# Qwiic_Pi_SHIM.net
KiCad netlist of a schematic drawn in EAGLE
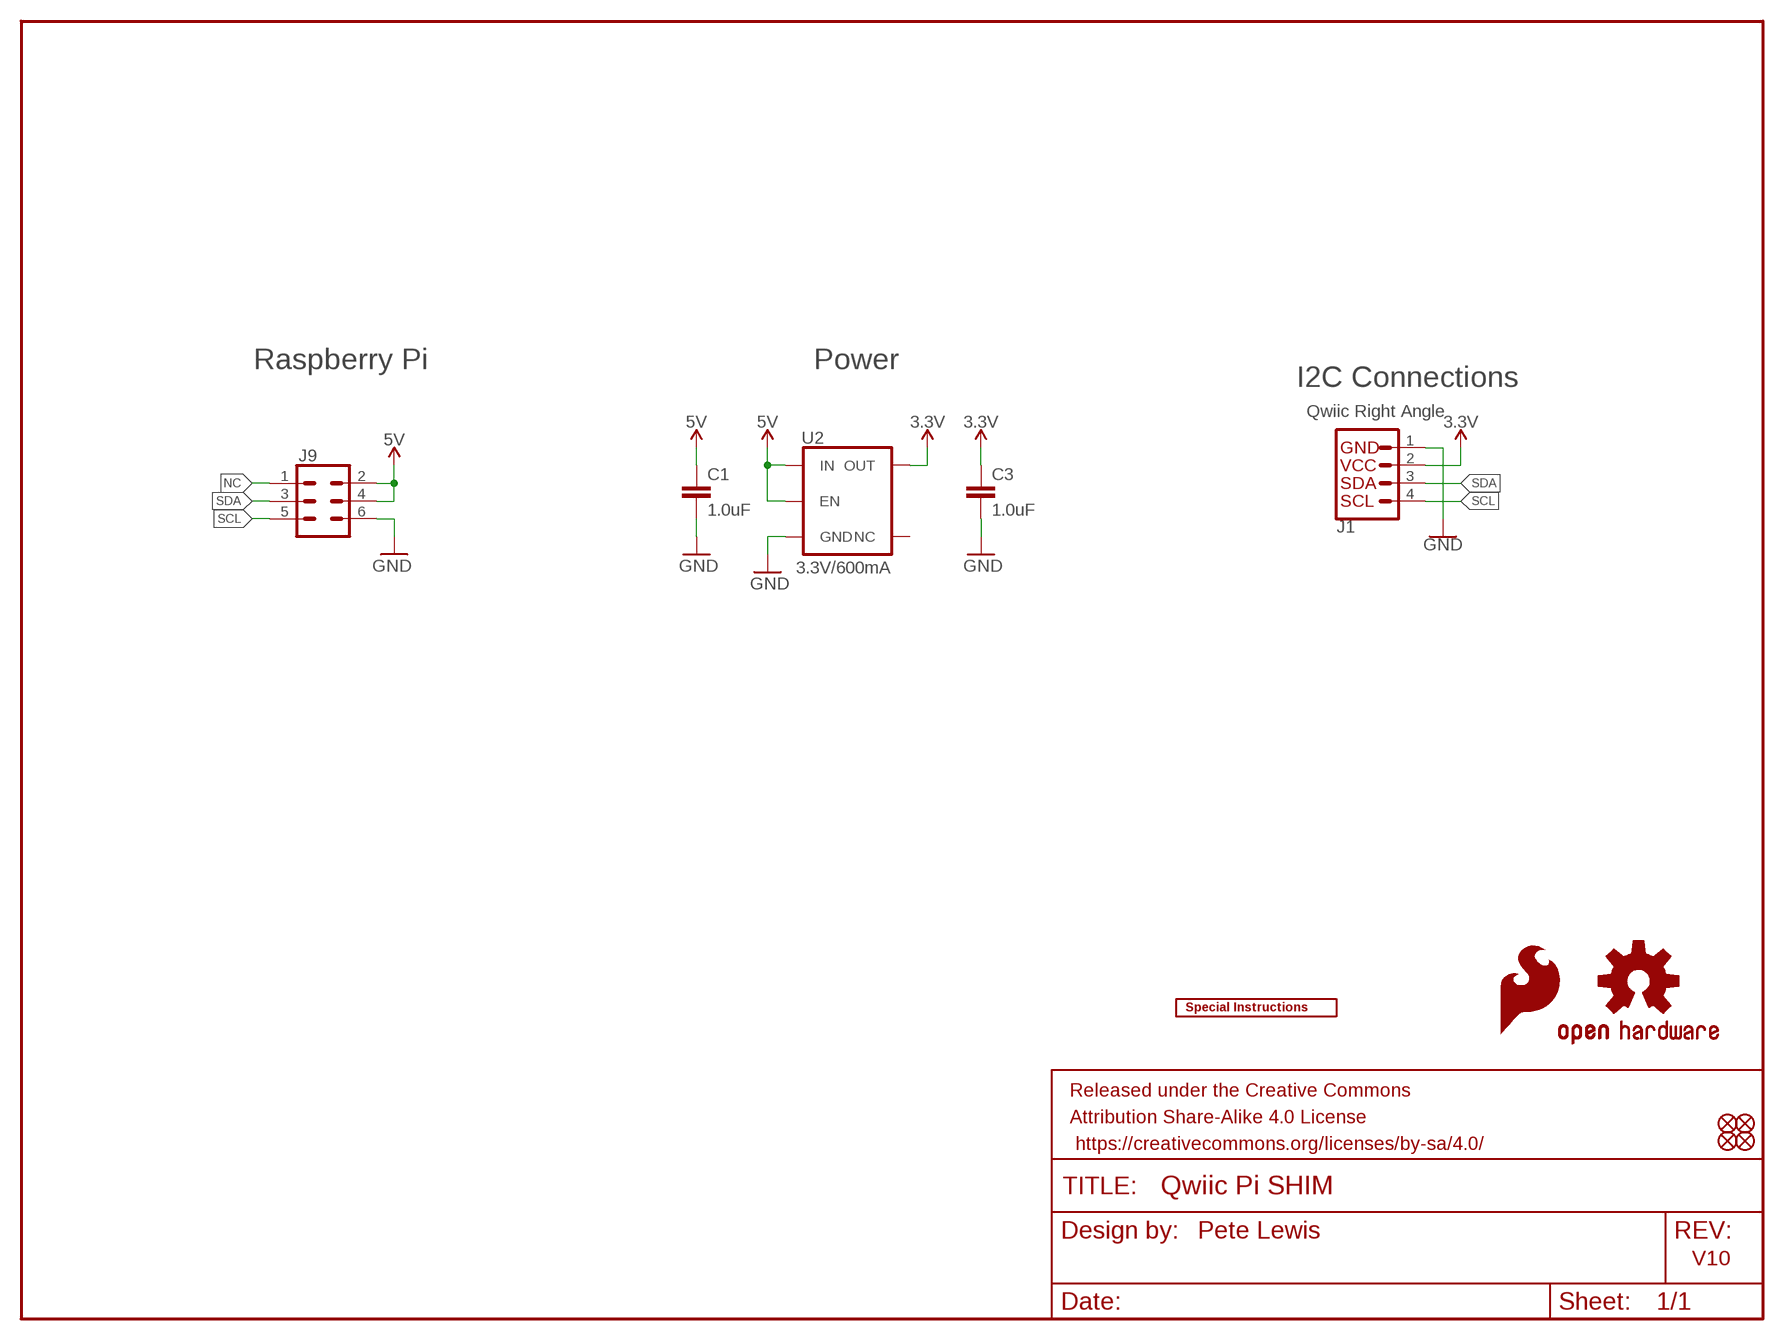
[diagram p0: schematic, sheet 1]

(export (version "E")
  (design (tool "Eeschema 10.0.6"))
  (components
    (comp (ref "C1")
      (value "1.0uF")
      (footprint "eagle-import:0603")
      (libsource (lib "eagle-import") (part "1.0UF-0603-16V-10%"))
    )
    (comp (ref "C3")
      (value "1.0uF")
      (footprint "eagle-import:0603")
      (libsource (lib "eagle-import") (part "1.0UF-0603-16V-10%"))
    )
    (comp (ref "FD1")
      (value "FIDUCIALUFIDUCIAL")
      (footprint "eagle-import:FIDUCIAL-MICRO")
      (libsource (lib "eagle-import") (part "FIDUCIALUFIDUCIAL"))
    )
    (comp (ref "FD2")
      (value "FIDUCIALUFIDUCIAL")
      (footprint "eagle-import:FIDUCIAL-MICRO")
      (libsource (lib "eagle-import") (part "FIDUCIALUFIDUCIAL"))
    )
    (comp (ref "FD3")
      (value "FIDUCIALUFIDUCIAL")
      (footprint "eagle-import:FIDUCIAL-MICRO")
      (libsource (lib "eagle-import") (part "FIDUCIALUFIDUCIAL"))
    )
    (comp (ref "FD4")
      (value "FIDUCIALUFIDUCIAL")
      (footprint "eagle-import:FIDUCIAL-MICRO")
      (libsource (lib "eagle-import") (part "FIDUCIALUFIDUCIAL"))
    )
    (comp (ref "FRAME1")
      (value "FRAME-LETTER")
      (footprint "eagle-import:CREATIVE_COMMONS")
      (libsource (lib "eagle-import") (part "FRAME-LETTER"))
    )
    (comp (ref "J1")
      (value "Qwiic Right Angle")
      (footprint "eagle-import:1X04_1MM_RA")
      (libsource (lib "eagle-import") (part "I2C_STANDARDQWIIC"))
    )
    (comp (ref "J9")
      (value "SPARKFUN-CONNECTORS_CONN_03X2SINGLE_SLOT-4MILS")
      (footprint "eagle-import:SPARKFUN-CONNECTORS_2X3-NS_PISHIM_LOCKING_SLOTS-4MILS")
      (libsource (lib "eagle-import") (part "SPARKFUN-CONNECTORS_CONN_03X2SINGLE_SLOT-4MILS"))
    )
    (comp (ref "LOGO1")
      (value "OSHW-LOGOMINI")
      (footprint "eagle-import:OSHW-LOGO-MINI")
      (libsource (lib "eagle-import") (part "OSHW-LOGOMINI"))
    )
    (comp (ref "U$1")
      (value "SFE_LOGO_FLAME.1_INCH")
      (footprint "eagle-import:SFE_LOGO_FLAME_.1")
      (libsource (lib "eagle-import") (part "SFE_LOGO_FLAME.1_INCH"))
    )
    (comp (ref "U$4")
      (value "SPECIAL_INSTRUCTIONS-ORDERING")
      (footprint "eagle-import:ORDERING_INSTRUCTIONS")
      (libsource (lib "eagle-import") (part "SPECIAL_INSTRUCTIONS-ORDERING"))
    )
    (comp (ref "U2")
      (value "3.3V/600mA")
      (footprint "eagle-import:SOT23-5")
      (libsource (lib "eagle-import") (part "V_REG_AP2112K-3.3V"))
    )
  )
  (nets
    (net (code "1") (name "3.3V") (class "Default")
      (node (ref "C3") (pin "1") (pinfunction "1_1") (pintype "passive"))
      (node (ref "J1") (pin "2") (pinfunction "2_2") (pintype "power_in"))
      (node (ref "U2") (pin "5") (pinfunction "OUT_5") (pintype "passive"))
    )
    (net (code "2") (name "5V") (class "Default")
      (node (ref "C1") (pin "1") (pinfunction "1_1") (pintype "passive"))
      (node (ref "J9") (pin "2") (pinfunction "2_2") (pintype "bidirectional"))
      (node (ref "J9") (pin "4") (pinfunction "4_4") (pintype "bidirectional"))
      (node (ref "U2") (pin "1") (pinfunction "IN_1") (pintype "input"))
      (node (ref "U2") (pin "3") (pinfunction "EN_3") (pintype "input"))
    )
    (net (code "3") (name "GND") (class "Default")
      (node (ref "C1") (pin "2") (pinfunction "2_2") (pintype "passive"))
      (node (ref "C3") (pin "2") (pinfunction "2_2") (pintype "passive"))
      (node (ref "J1") (pin "1") (pinfunction "1_1") (pintype "power_in"))
      (node (ref "J9") (pin "6") (pinfunction "6_6") (pintype "bidirectional"))
      (node (ref "U2") (pin "2") (pinfunction "GND_2") (pintype "input"))
    )
    (net (code "4") (name "NC") (class "Default")
      (node (ref "J9") (pin "1") (pinfunction "1_1") (pintype "bidirectional"))
    )
    (net (code "5") (name "SCL") (class "Default")
      (node (ref "J1") (pin "4") (pinfunction "4_4") (pintype "passive"))
      (node (ref "J9") (pin "5") (pinfunction "5_5") (pintype "bidirectional"))
    )
    (net (code "6") (name "SDA") (class "Default")
      (node (ref "J1") (pin "3") (pinfunction "3_3") (pintype "passive"))
      (node (ref "J9") (pin "3") (pinfunction "3_3") (pintype "bidirectional"))
    )
    (net (code "7") (name "unconnected-(U2-NC-Pad4)") (class "Default")
      (node (ref "U2") (pin "4") (pinfunction "NC_4") (pintype "no_connect"))
    )
  )
)
